# interface.net
KiCad netlist of a schematic drawn in EAGLE
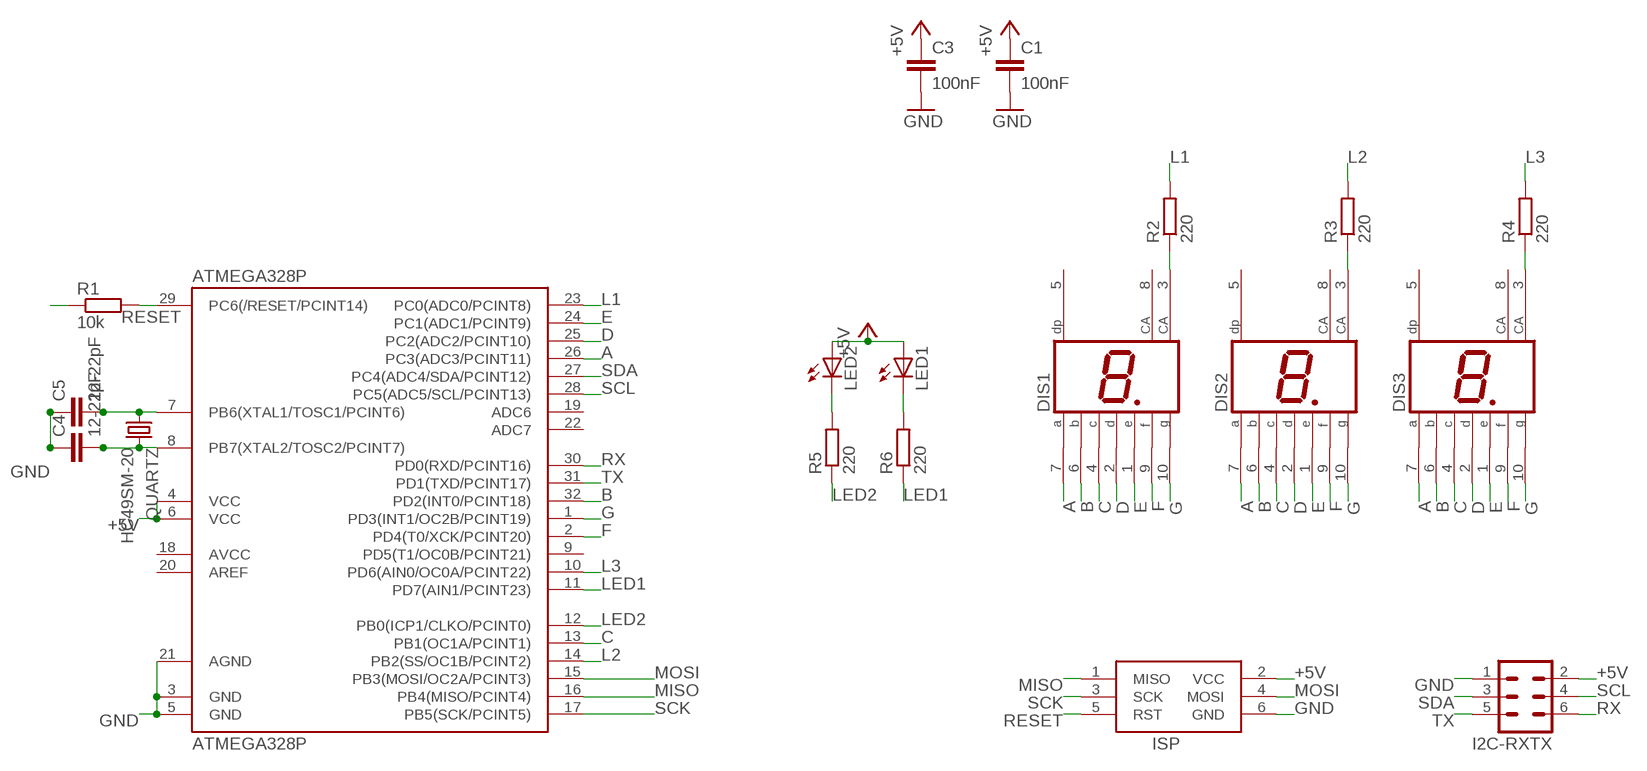
[diagram p0: schematic, sheet 1]

(export (version "E")
  (design (tool "Eeschema 10.0.6"))
  (components
    (comp (ref "ATMEGA328P")
      (value "ATMEGA328P")
      (footprint "eagle-import:TQFP32-08")
      (libsource (lib "eagle-import") (part "MEGA48/88/168-AU"))
    )
    (comp (ref "C1")
      (value "100nF")
      (footprint "eagle-import:C0805")
      (libsource (lib "eagle-import") (part "C-EUC0805"))
    )
    (comp (ref "C3")
      (value "100nF")
      (footprint "eagle-import:C0805")
      (libsource (lib "eagle-import") (part "C-EUC0805"))
    )
    (comp (ref "C4")
      (value "12-22pF")
      (footprint "eagle-import:C0805")
      (libsource (lib "eagle-import") (part "C-EUC0805"))
    )
    (comp (ref "C5")
      (value "12-22pF")
      (footprint "eagle-import:C0805")
      (libsource (lib "eagle-import") (part "C-EUC0805"))
    )
    (comp (ref "DIS1")
      (value "HD-H101")
      (footprint "eagle-import:HDSP-M")
      (libsource (lib "eagle-import") (part "HD-H101"))
    )
    (comp (ref "DIS2")
      (value "HD-H101")
      (footprint "eagle-import:HDSP-M")
      (libsource (lib "eagle-import") (part "HD-H101"))
    )
    (comp (ref "DIS3")
      (value "HD-H101")
      (footprint "eagle-import:HDSP-M")
      (libsource (lib "eagle-import") (part "HD-H101"))
    )
    (comp (ref "I2C-RXTX")
      (value "MA03-2")
      (footprint "eagle-import:MA03-2")
      (libsource (lib "eagle-import") (part "MA03-2"))
    )
    (comp (ref "ISP")
      (value "AVRISP-6")
      (footprint "eagle-import:AVRISP")
      (libsource (lib "eagle-import") (part "AVRISP-6"))
    )
    (comp (ref "LED1")
      (value "LED5MM")
      (footprint "eagle-import:LED5MM")
      (libsource (lib "eagle-import") (part "LED5MM"))
    )
    (comp (ref "LED2")
      (value "LED5MM")
      (footprint "eagle-import:LED5MM")
      (libsource (lib "eagle-import") (part "LED5MM"))
    )
    (comp (ref "QUARTZ")
      (value "HC49SM-20")
      (footprint "eagle-import:HC49UP")
      (libsource (lib "eagle-import") (part "CRYSTALHC49UP"))
    )
    (comp (ref "R1")
      (value "10k")
      (footprint "eagle-import:R0805")
      (libsource (lib "eagle-import") (part "R-EU_R0805"))
    )
    (comp (ref "R2")
      (value "220")
      (footprint "eagle-import:R0805")
      (libsource (lib "eagle-import") (part "R-EU_R0805"))
    )
    (comp (ref "R3")
      (value "220")
      (footprint "eagle-import:R0805")
      (libsource (lib "eagle-import") (part "R-EU_R0805"))
    )
    (comp (ref "R4")
      (value "220")
      (footprint "eagle-import:R0805")
      (libsource (lib "eagle-import") (part "R-EU_R0805"))
    )
    (comp (ref "R5")
      (value "220")
      (footprint "eagle-import:R0805")
      (libsource (lib "eagle-import") (part "R-EU_R0805"))
    )
    (comp (ref "R6")
      (value "220")
      (footprint "eagle-import:R0805")
      (libsource (lib "eagle-import") (part "R-EU_R0805"))
    )
  )
  (nets
    (net (code "1") (name "+5V") (class "Default")
      (node (ref "ATMEGA328P") (pin "4") (pinfunction "VCC_4") (pintype "power_in"))
      (node (ref "ATMEGA328P") (pin "6") (pinfunction "VCC_6") (pintype "power_in"))
      (node (ref "C1") (pin "1") (pinfunction "1_1") (pintype "passive"))
      (node (ref "C3") (pin "1") (pinfunction "1_1") (pintype "passive"))
      (node (ref "I2C-RXTX") (pin "2") (pinfunction "2_2") (pintype "passive"))
      (node (ref "ISP") (pin "2") (pinfunction "VCC_2") (pintype "power_in"))
      (node (ref "LED1") (pin "A") (pinfunction "A_A") (pintype "passive"))
      (node (ref "LED2") (pin "A") (pinfunction "A_A") (pintype "passive"))
      (node (ref "R1") (pin "1") (pinfunction "1_1") (pintype "passive"))
    )
    (net (code "2") (name "/A") (class "Default")
      (node (ref "ATMEGA328P") (pin "26") (pinfunction "PC3(ADC3/PCINT11)_26") (pintype "bidirectional"))
      (node (ref "DIS1") (pin "7") (pinfunction "A_7") (pintype "passive"))
      (node (ref "DIS2") (pin "7") (pinfunction "A_7") (pintype "passive"))
      (node (ref "DIS3") (pin "7") (pinfunction "A_7") (pintype "passive"))
    )
    (net (code "3") (name "/B") (class "Default")
      (node (ref "ATMEGA328P") (pin "32") (pinfunction "PD2(INT0/PCINT18)_32") (pintype "bidirectional"))
      (node (ref "DIS1") (pin "6") (pinfunction "B_6") (pintype "passive"))
      (node (ref "DIS2") (pin "6") (pinfunction "B_6") (pintype "passive"))
      (node (ref "DIS3") (pin "6") (pinfunction "B_6") (pintype "passive"))
    )
    (net (code "4") (name "/C") (class "Default")
      (node (ref "ATMEGA328P") (pin "13") (pinfunction "PB1(OC1A/PCINT1)_13") (pintype "bidirectional"))
      (node (ref "DIS1") (pin "4") (pinfunction "C_4") (pintype "passive"))
      (node (ref "DIS2") (pin "4") (pinfunction "C_4") (pintype "passive"))
      (node (ref "DIS3") (pin "4") (pinfunction "C_4") (pintype "passive"))
    )
    (net (code "5") (name "/D") (class "Default")
      (node (ref "ATMEGA328P") (pin "25") (pinfunction "PC2(ADC2/PCINT10)_25") (pintype "bidirectional"))
      (node (ref "DIS1") (pin "2") (pinfunction "D_2") (pintype "passive"))
      (node (ref "DIS2") (pin "2") (pinfunction "D_2") (pintype "passive"))
      (node (ref "DIS3") (pin "2") (pinfunction "D_2") (pintype "passive"))
    )
    (net (code "6") (name "/E") (class "Default")
      (node (ref "ATMEGA328P") (pin "24") (pinfunction "PC1(ADC1/PCINT9)_24") (pintype "bidirectional"))
      (node (ref "DIS1") (pin "1") (pinfunction "E_1") (pintype "passive"))
      (node (ref "DIS2") (pin "1") (pinfunction "E_1") (pintype "passive"))
      (node (ref "DIS3") (pin "1") (pinfunction "E_1") (pintype "passive"))
    )
    (net (code "7") (name "/F") (class "Default")
      (node (ref "ATMEGA328P") (pin "2") (pinfunction "PD4(T0/XCK/PCINT20)_2") (pintype "bidirectional"))
      (node (ref "DIS1") (pin "9") (pinfunction "F_9") (pintype "passive"))
      (node (ref "DIS2") (pin "9") (pinfunction "F_9") (pintype "passive"))
      (node (ref "DIS3") (pin "9") (pinfunction "F_9") (pintype "passive"))
    )
    (net (code "8") (name "/G") (class "Default")
      (node (ref "ATMEGA328P") (pin "1") (pinfunction "PD3(INT1/OC2B/PCINT19)_1") (pintype "bidirectional"))
      (node (ref "DIS1") (pin "10") (pinfunction "G_10") (pintype "passive"))
      (node (ref "DIS2") (pin "10") (pinfunction "G_10") (pintype "passive"))
      (node (ref "DIS3") (pin "10") (pinfunction "G_10") (pintype "passive"))
    )
    (net (code "9") (name "/L1") (class "Default")
      (node (ref "ATMEGA328P") (pin "23") (pinfunction "PC0(ADC0/PCINT8)_23") (pintype "bidirectional"))
      (node (ref "R2") (pin "2") (pinfunction "2_2") (pintype "passive"))
    )
    (net (code "10") (name "/L2") (class "Default")
      (node (ref "ATMEGA328P") (pin "14") (pinfunction "PB2(SS/OC1B/PCINT2)_14") (pintype "bidirectional"))
      (node (ref "R3") (pin "2") (pinfunction "2_2") (pintype "passive"))
    )
    (net (code "11") (name "/L3") (class "Default")
      (node (ref "ATMEGA328P") (pin "10") (pinfunction "PD6(AIN0/OC0A/PCINT22)_10") (pintype "bidirectional"))
      (node (ref "R4") (pin "2") (pinfunction "2_2") (pintype "passive"))
    )
    (net (code "12") (name "/LED1") (class "Default")
      (node (ref "ATMEGA328P") (pin "11") (pinfunction "PD7(AIN1/PCINT23)_11") (pintype "bidirectional"))
      (node (ref "R6") (pin "1") (pinfunction "1_1") (pintype "passive"))
    )
    (net (code "13") (name "/LED2") (class "Default")
      (node (ref "ATMEGA328P") (pin "12") (pinfunction "PB0(ICP1/CLKO/PCINT0)_12") (pintype "bidirectional"))
      (node (ref "R5") (pin "1") (pinfunction "1_1") (pintype "passive"))
    )
    (net (code "14") (name "/MISO") (class "Default")
      (node (ref "ATMEGA328P") (pin "16") (pinfunction "PB4(MISO/PCINT4)_16") (pintype "bidirectional"))
      (node (ref "ISP") (pin "1") (pinfunction "MISO_1") (pintype "input"))
    )
    (net (code "15") (name "/MOSI") (class "Default")
      (node (ref "ATMEGA328P") (pin "15") (pinfunction "PB3(MOSI/OC2A/PCINT3)_15") (pintype "bidirectional"))
      (node (ref "ISP") (pin "4") (pinfunction "MOSI_4") (pintype "output"))
    )
    (net (code "16") (name "/RESET") (class "Default")
      (node (ref "ATMEGA328P") (pin "29") (pinfunction "PC6(/RESET/PCINT14)_29") (pintype "bidirectional"))
      (node (ref "ISP") (pin "5") (pinfunction "RST_5") (pintype "output"))
      (node (ref "R1") (pin "2") (pinfunction "2_2") (pintype "passive"))
    )
    (net (code "17") (name "/RX") (class "Default")
      (node (ref "ATMEGA328P") (pin "30") (pinfunction "PD0(RXD/PCINT16)_30") (pintype "bidirectional"))
      (node (ref "I2C-RXTX") (pin "6") (pinfunction "6_6") (pintype "passive"))
    )
    (net (code "18") (name "/SCK") (class "Default")
      (node (ref "ATMEGA328P") (pin "17") (pinfunction "PB5(SCK/PCINT5)_17") (pintype "bidirectional"))
      (node (ref "ISP") (pin "3") (pinfunction "SCK_3") (pintype "output"))
    )
    (net (code "19") (name "/SCL") (class "Default")
      (node (ref "ATMEGA328P") (pin "28") (pinfunction "PC5(ADC5/SCL/PCINT13)_28") (pintype "bidirectional"))
      (node (ref "I2C-RXTX") (pin "4") (pinfunction "4_4") (pintype "passive"))
    )
    (net (code "20") (name "/SDA") (class "Default")
      (node (ref "ATMEGA328P") (pin "27") (pinfunction "PC4(ADC4/SDA/PCINT12)_27") (pintype "bidirectional"))
      (node (ref "I2C-RXTX") (pin "3") (pinfunction "3_3") (pintype "passive"))
    )
    (net (code "21") (name "/TX") (class "Default")
      (node (ref "ATMEGA328P") (pin "31") (pinfunction "PD1(TXD/PCINT17)_31") (pintype "bidirectional"))
      (node (ref "I2C-RXTX") (pin "5") (pinfunction "5_5") (pintype "passive"))
    )
    (net (code "22") (name "GND") (class "Default")
      (node (ref "ATMEGA328P") (pin "21") (pinfunction "AGND_21") (pintype "power_in"))
      (node (ref "ATMEGA328P") (pin "3") (pinfunction "GND_3") (pintype "power_in"))
      (node (ref "ATMEGA328P") (pin "5") (pinfunction "GND_5") (pintype "power_in"))
      (node (ref "C1") (pin "2") (pinfunction "2_2") (pintype "passive"))
      (node (ref "C3") (pin "2") (pinfunction "2_2") (pintype "passive"))
      (node (ref "C4") (pin "1") (pinfunction "1_1") (pintype "passive"))
      (node (ref "C5") (pin "1") (pinfunction "1_1") (pintype "passive"))
      (node (ref "I2C-RXTX") (pin "1") (pinfunction "1_1") (pintype "passive"))
      (node (ref "ISP") (pin "6") (pinfunction "GND_6") (pintype "power_in"))
    )
    (net (code "23") (name "Net-(ATMEGA328P-PB6(XTAL1{slash}TOSC1{slash}PCINT6))") (class "Default")
      (node (ref "ATMEGA328P") (pin "7") (pinfunction "PB6(XTAL1/TOSC1/PCINT6)_7") (pintype "bidirectional"))
      (node (ref "C5") (pin "2") (pinfunction "2_2") (pintype "passive"))
      (node (ref "QUARTZ") (pin "1") (pinfunction "1_1") (pintype "passive"))
    )
    (net (code "24") (name "Net-(ATMEGA328P-PB7(XTAL2{slash}TOSC2{slash}PCINT7))") (class "Default")
      (node (ref "ATMEGA328P") (pin "8") (pinfunction "PB7(XTAL2/TOSC2/PCINT7)_8") (pintype "bidirectional"))
      (node (ref "C4") (pin "2") (pinfunction "2_2") (pintype "passive"))
      (node (ref "QUARTZ") (pin "2") (pinfunction "2_2") (pintype "passive"))
    )
    (net (code "25") (name "Net-(DIS1-CA-Pad3)") (class "Default")
      (node (ref "DIS1") (pin "3") (pinfunction "CA_3") (pintype "passive"))
      (node (ref "R2") (pin "1") (pinfunction "1_1") (pintype "passive"))
    )
    (net (code "26") (name "Net-(DIS2-CA-Pad3)") (class "Default")
      (node (ref "DIS2") (pin "3") (pinfunction "CA_3") (pintype "passive"))
      (node (ref "R3") (pin "1") (pinfunction "1_1") (pintype "passive"))
    )
    (net (code "27") (name "Net-(DIS3-CA-Pad3)") (class "Default")
      (node (ref "DIS3") (pin "3") (pinfunction "CA_3") (pintype "passive"))
      (node (ref "R4") (pin "1") (pinfunction "1_1") (pintype "passive"))
    )
    (net (code "28") (name "Net-(LED1-C)") (class "Default")
      (node (ref "LED1") (pin "K") (pinfunction "C_K") (pintype "passive"))
      (node (ref "R6") (pin "2") (pinfunction "2_2") (pintype "passive"))
    )
    (net (code "29") (name "Net-(LED2-C)") (class "Default")
      (node (ref "LED2") (pin "K") (pinfunction "C_K") (pintype "passive"))
      (node (ref "R5") (pin "2") (pinfunction "2_2") (pintype "passive"))
    )
    (net (code "30") (name "unconnected-(ATMEGA328P-ADC6-Pad19)") (class "Default")
      (node (ref "ATMEGA328P") (pin "19") (pinfunction "ADC6_19") (pintype "passive"))
    )
    (net (code "31") (name "unconnected-(ATMEGA328P-ADC7-Pad22)") (class "Default")
      (node (ref "ATMEGA328P") (pin "22") (pinfunction "ADC7_22") (pintype "passive"))
    )
    (net (code "32") (name "unconnected-(ATMEGA328P-AREF-Pad20)") (class "Default")
      (node (ref "ATMEGA328P") (pin "20") (pinfunction "AREF_20") (pintype "passive"))
    )
    (net (code "33") (name "unconnected-(ATMEGA328P-AVCC-Pad18)") (class "Default")
      (node (ref "ATMEGA328P") (pin "18") (pinfunction "AVCC_18") (pintype "passive"))
    )
    (net (code "34") (name "unconnected-(ATMEGA328P-PD5(T1{slash}OC0B{slash}PCINT21)-Pad9)") (class "Default")
      (node (ref "ATMEGA328P") (pin "9") (pinfunction "PD5(T1/OC0B/PCINT21)_9") (pintype "bidirectional"))
    )
    (net (code "35") (name "unconnected-(DIS1-CA-Pad8)") (class "Default")
      (node (ref "DIS1") (pin "8") (pinfunction "CA_8") (pintype "passive"))
    )
    (net (code "36") (name "unconnected-(DIS1-DP-Pad5)") (class "Default")
      (node (ref "DIS1") (pin "5") (pinfunction "DP_5") (pintype "passive"))
    )
    (net (code "37") (name "unconnected-(DIS2-CA-Pad8)") (class "Default")
      (node (ref "DIS2") (pin "8") (pinfunction "CA_8") (pintype "passive"))
    )
    (net (code "38") (name "unconnected-(DIS2-DP-Pad5)") (class "Default")
      (node (ref "DIS2") (pin "5") (pinfunction "DP_5") (pintype "passive"))
    )
    (net (code "39") (name "unconnected-(DIS3-CA-Pad8)") (class "Default")
      (node (ref "DIS3") (pin "8") (pinfunction "CA_8") (pintype "passive"))
    )
    (net (code "40") (name "unconnected-(DIS3-DP-Pad5)") (class "Default")
      (node (ref "DIS3") (pin "5") (pinfunction "DP_5") (pintype "passive"))
    )
  )
)
